# ArduitsyR3.net
KiCad netlist of a schematic drawn in EAGLE
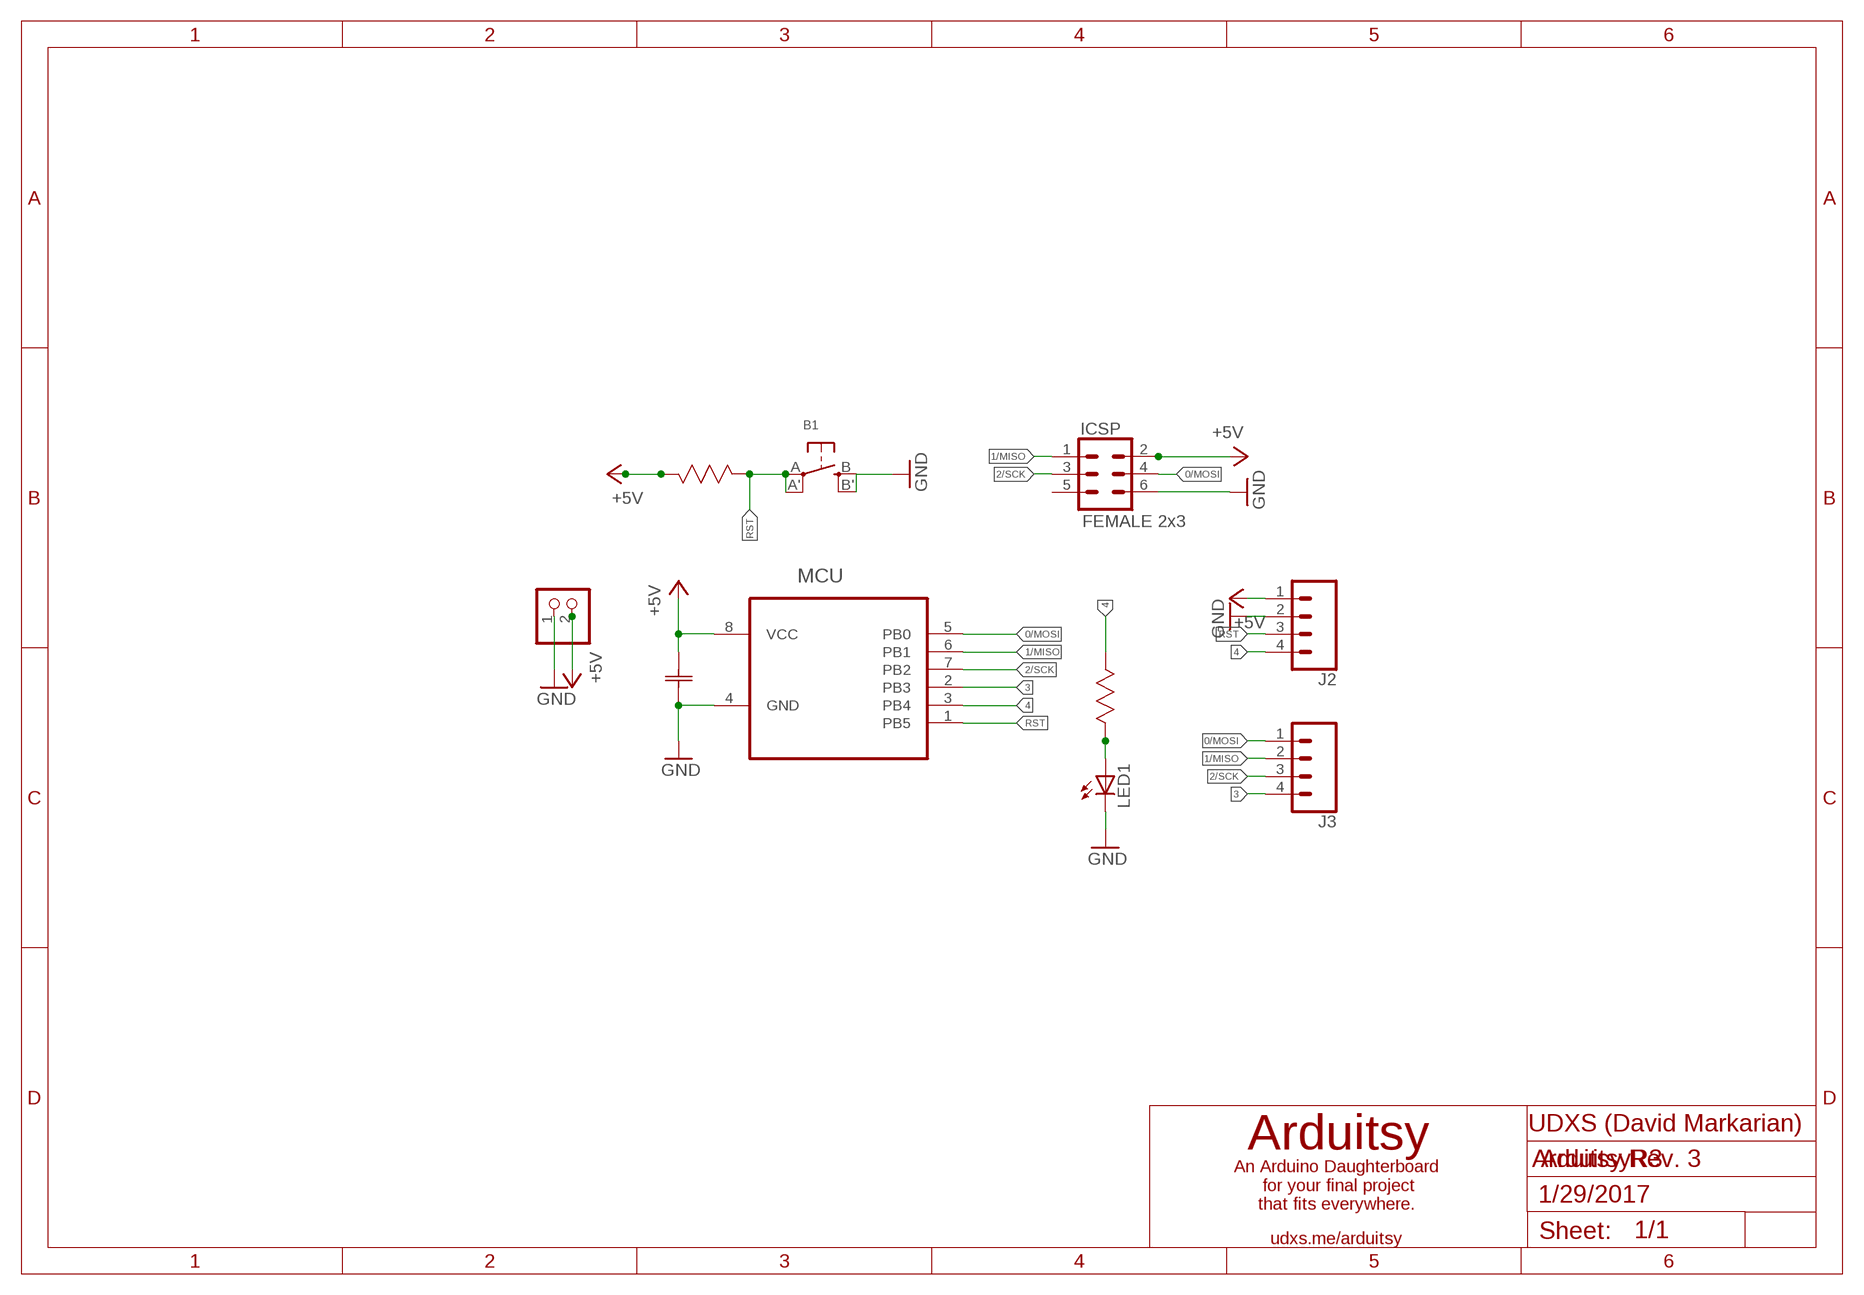
[diagram p0: schematic, sheet 1]

(export (version "E")
  (design (tool "Eeschema 10.0.6"))
  (components
    (comp (ref "B1")
      (value "SWITCH_TACT_SMT")
      (footprint "eagle-import:EVQ-Q2")
      (libsource (lib "eagle-import") (part "SWITCH_TACT_SMT"))
    )
    (comp (ref "C1")
      (value "0.1µF")
      (footprint "eagle-import:CAPC2012X94N")
      (fields (field (name "MPN") "0805YC104KAT4A") (field (name "TOLERANCE") "±10%"))
      (libsource (lib "eagle-import") (part "0805YC104KAT4A"))
    )
    (comp (ref "CN1")
      (value "JST_2PIN")
      (footprint "eagle-import:JSTPH2")
      (libsource (lib "eagle-import") (part "JST_2PIN"))
    )
    (comp (ref "ICSP")
      (value "FEMALE 2x3")
      (footprint "eagle-import:2X3")
      (libsource (lib "eagle-import") (part "CONN_03X2FEMALE"))
    )
    (comp (ref "J2")
      (value "CONN_04")
      (footprint "eagle-import:1X04")
      (libsource (lib "eagle-import") (part "CONN_04"))
    )
    (comp (ref "J3")
      (value "CONN_04")
      (footprint "eagle-import:1X04")
      (libsource (lib "eagle-import") (part "CONN_04"))
    )
    (comp (ref "LED1")
      (value "LEDCHIPLED_0805")
      (footprint "eagle-import:CHIPLED_0805")
      (libsource (lib "eagle-import") (part "LEDCHIPLED_0805"))
    )
    (comp (ref "MCU")
      (value "ATTINY85-20SU")
      (footprint "eagle-import:SOIC127P798X216-8N")
      (libsource (lib "eagle-import") (part "ATTINY85-20SU"))
    )
    (comp (ref "R1")
      (value "10K Ohms")
      (footprint "eagle-import:RESC2013X65N")
      (fields (field (name "MPN") "MC0.1W08051%10K") (field (name "TOLERANCE") "±1%"))
      (libsource (lib "eagle-import") (part "MC0.1W08051%10K"))
    )
    (comp (ref "R2")
      (value "10K Ohms")
      (footprint "eagle-import:RESC2013X65N")
      (fields (field (name "MPN") "MC0.1W08051%10K") (field (name "TOLERANCE") "±1%"))
      (libsource (lib "eagle-import") (part "MC0.1W08051%10K"))
    )
  )
  (nets
    (net (code "1") (name "+5V") (class "Default")
      (node (ref "C1") (pin "1") (pinfunction "C1_1") (pintype "passive"))
      (node (ref "CN1") (pin "2") (pinfunction "2_2") (pintype "passive"))
      (node (ref "ICSP") (pin "2") (pinfunction "2_2") (pintype "bidirectional"))
      (node (ref "J2") (pin "1") (pinfunction "1_1") (pintype "passive"))
      (node (ref "MCU") (pin "8") (pinfunction "VCC_8") (pintype "power_in"))
      (node (ref "R1") (pin "1") (pinfunction "R1_1") (pintype "passive"))
    )
    (net (code "2") (name "0{slash}MOSI") (class "Default")
      (node (ref "ICSP") (pin "4") (pinfunction "4_4") (pintype "bidirectional"))
      (node (ref "J3") (pin "1") (pinfunction "1_1") (pintype "passive"))
      (node (ref "MCU") (pin "5") (pinfunction "PB0_5") (pintype "bidirectional"))
    )
    (net (code "3") (name "1{slash}MISO") (class "Default")
      (node (ref "ICSP") (pin "1") (pinfunction "1_1") (pintype "bidirectional"))
      (node (ref "J3") (pin "2") (pinfunction "2_2") (pintype "passive"))
      (node (ref "MCU") (pin "6") (pinfunction "PB1_6") (pintype "bidirectional"))
    )
    (net (code "4") (name "2{slash}SCK") (class "Default")
      (node (ref "ICSP") (pin "3") (pinfunction "3_3") (pintype "bidirectional"))
      (node (ref "J3") (pin "3") (pinfunction "3_3") (pintype "passive"))
      (node (ref "MCU") (pin "7") (pinfunction "PB2_7") (pintype "bidirectional"))
    )
    (net (code "5") (name "3") (class "Default")
      (node (ref "J3") (pin "4") (pinfunction "4_4") (pintype "passive"))
      (node (ref "MCU") (pin "2") (pinfunction "PB3_2") (pintype "bidirectional"))
    )
    (net (code "6") (name "4") (class "Default")
      (node (ref "J2") (pin "4") (pinfunction "4_4") (pintype "passive"))
      (node (ref "MCU") (pin "3") (pinfunction "PB4_3") (pintype "bidirectional"))
      (node (ref "R2") (pin "1") (pinfunction "R1_1") (pintype "passive"))
    )
    (net (code "7") (name "GND") (class "Default")
      (node (ref "B1") (pin "B") (pinfunction "S_B") (pintype "passive"))
      (node (ref "B1") (pin "B'") (pinfunction "S1_B'") (pintype "passive"))
      (node (ref "C1") (pin "2") (pinfunction "C2_2") (pintype "passive"))
      (node (ref "CN1") (pin "1") (pinfunction "1_1") (pintype "passive"))
      (node (ref "ICSP") (pin "6") (pinfunction "6_6") (pintype "bidirectional"))
      (node (ref "J2") (pin "2") (pinfunction "2_2") (pintype "passive"))
      (node (ref "LED1") (pin "C") (pinfunction "C_C") (pintype "passive"))
      (node (ref "MCU") (pin "4") (pinfunction "GND_4") (pintype "passive"))
    )
    (net (code "8") (name "Net-(R2-R2)") (class "Default")
      (node (ref "LED1") (pin "A") (pinfunction "A_A") (pintype "passive"))
      (node (ref "R2") (pin "2") (pinfunction "R2_2") (pintype "passive"))
    )
    (net (code "9") (name "RST") (class "Default")
      (node (ref "B1") (pin "A") (pinfunction "P_A") (pintype "passive"))
      (node (ref "B1") (pin "A'") (pinfunction "P1_A'") (pintype "passive"))
      (node (ref "J2") (pin "3") (pinfunction "3_3") (pintype "passive"))
      (node (ref "MCU") (pin "1") (pinfunction "PB5_1") (pintype "bidirectional"))
      (node (ref "R1") (pin "2") (pinfunction "R2_2") (pintype "passive"))
    )
    (net (code "10") (name "unconnected-(ICSP-Pad5)") (class "Default")
      (node (ref "ICSP") (pin "5") (pinfunction "5_5") (pintype "bidirectional"))
    )
  )
)
